# Sensor.net
KiCad netlist of a schematic drawn in Altium Designer
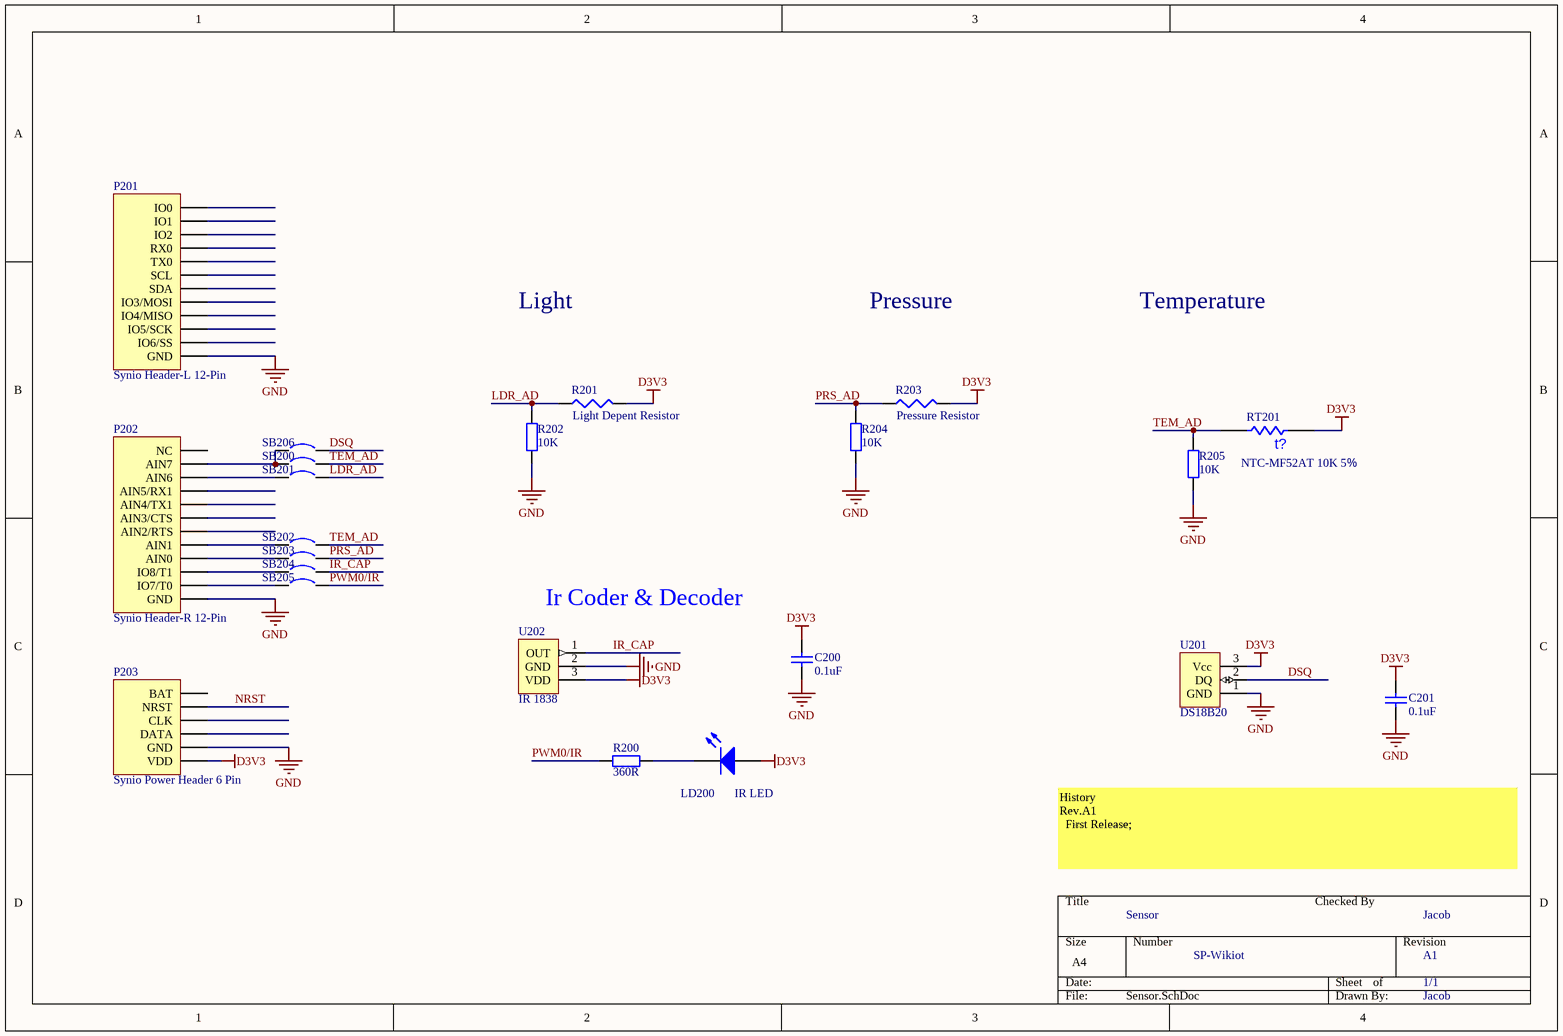
[diagram p0: Sensor.SchDoc]

(export (version "E")
  (design (tool "Eeschema 10.0.6"))
  (components
    (comp (ref "C200")
      (value "0.1uF")
      (footprint "0603M")
      (description "Capacitor")
      (fields (field (name "PUBLISHER") "Altium Limited"))
      (libsource (lib "Miscellaneous Devices") (part "Cap"))
    )
    (comp (ref "C201")
      (value "0.1uF")
      (footprint "0603M")
      (description "Capacitor")
      (fields (field (name "PUBLISHER") "Altium Limited"))
      (libsource (lib "Miscellaneous Devices") (part "Cap"))
    )
    (comp (ref "LD200")
      (value "IR LED")
      (footprint "HDR1X2/2.54mm")
      (description "Typical RED, GREEN, YELLOW, AMBER GaAs LED")
      (fields (field (name "PUBLISHER") "Altium Limited"))
      (libsource (lib "CT107D_SUDA") (part "LED"))
    )
    (comp (ref "P201")
      (value "Synio Header-L 12-Pin")
      (footprint "HDR1X12")
      (description "Synio Header-L, 12-Pin")
      (fields (field (name "PUBLISHER") "Altium Limited"))
      (libsource (lib "Connector") (part "Synio Header-L 12-Pin"))
    )
    (comp (ref "P202")
      (value "Synio Header-R 12-Pin")
      (footprint "HDR1X12")
      (description "Synio Header-R, 12-Pin")
      (fields (field (name "PUBLISHER") "Altium Limited"))
      (libsource (lib "Connector") (part "Synio Header-R 12-Pin"))
    )
    (comp (ref "P203")
      (value "Synio Power Header 6 Pin")
      (footprint "HDR1X6/2.54MM")
      (libsource (lib "Connector") (part "Synio Power Header 6 Pin"))
    )
    (comp (ref "R200")
      (value "360R")
      (footprint "0603M")
      (description "Resistor")
      (fields (field (name "PUBLISHER") "Altium Limited"))
      (libsource (lib "CT107D_SUDA") (part "Res"))
    )
    (comp (ref "R201")
      (value "Light Depent Resistor")
      (footprint "AXIAL-0.4")
      (description "Resistor")
      (fields (field (name "Comment") "Res3") (field (name "PUBLISHER") "Altium Limited"))
      (libsource (lib "Miscellaneous Devices") (part "Res3"))
    )
    (comp (ref "R202")
      (value "10K")
      (footprint "R0603")
      (description "Resistor")
      (fields (field (name "PUBLISHER") "Altium Limited"))
      (libsource (lib "Miscellaneous Devices") (part "Res2"))
    )
    (comp (ref "R203")
      (value "Pressure Resistor")
      (footprint "HDR1X2/2.54mm")
      (description "Resistor")
      (fields (field (name "Comment") "Res3") (field (name "PUBLISHER") "Altium Limited"))
      (libsource (lib "Miscellaneous Devices") (part "Res3"))
    )
    (comp (ref "R204")
      (value "10K")
      (footprint "R0603")
      (description "Resistor")
      (fields (field (name "PUBLISHER") "Altium Limited"))
      (libsource (lib "Miscellaneous Devices") (part "Res2"))
    )
    (comp (ref "R205")
      (value "10K")
      (footprint "R0603")
      (description "Resistor")
      (fields (field (name "PUBLISHER") "Altium Limited"))
      (libsource (lib "Miscellaneous Devices") (part "Res2"))
    )
    (comp (ref "RT201")
      (value "NTC-MF52AT 10K 5％")
      (footprint "HDR1X2/2.54mm")
      (description "Thermistor")
      (fields (field (name "PUBLISHER") "Altium Limited"))
      (libsource (lib "Miscellaneous Devices") (part "Res Thermal"))
    )
    (comp (ref "SB200")
      (value "Circuit Breaker")
      (footprint "JP2_SMD")
      (fields (field (name "PUBLISHER") "Altium Limited"))
      (libsource (lib "Misc") (part "Circuit Breaker"))
    )
    (comp (ref "SB201")
      (value "Circuit Breaker")
      (footprint "JP2_SMD")
      (fields (field (name "PUBLISHER") "Altium Limited"))
      (libsource (lib "Misc") (part "Circuit Breaker"))
    )
    (comp (ref "SB202")
      (value "Circuit Breaker")
      (footprint "JP2_SMD")
      (fields (field (name "PUBLISHER") "Altium Limited"))
      (libsource (lib "Misc") (part "Circuit Breaker"))
    )
    (comp (ref "SB203")
      (value "Circuit Breaker")
      (footprint "JP2_SMD")
      (fields (field (name "PUBLISHER") "Altium Limited"))
      (libsource (lib "Misc") (part "Circuit Breaker"))
    )
    (comp (ref "SB204")
      (value "Circuit Breaker")
      (footprint "JP2_SMD")
      (fields (field (name "PUBLISHER") "Altium Limited"))
      (libsource (lib "Misc") (part "Circuit Breaker"))
    )
    (comp (ref "SB205")
      (value "Circuit Breaker")
      (footprint "JP2_SMD")
      (fields (field (name "PUBLISHER") "Altium Limited"))
      (libsource (lib "Misc") (part "Circuit Breaker"))
    )
    (comp (ref "SB206")
      (value "Circuit Breaker")
      (footprint "JP2_SMD")
      (fields (field (name "PUBLISHER") "Altium Limited"))
      (libsource (lib "Misc") (part "Circuit Breaker"))
    )
    (comp (ref "U201")
      (value "DS18B20")
      (footprint "TO92")
      (description "Programmable Resolution  1-Wire Digital Thermometer")
      (fields (field (name "PUBLISHER") "Altium Limited"))
      (libsource (lib "CT107D_SUDA") (part "DS18B20"))
    )
    (comp (ref "U202")
      (value "IR 1838")
      (footprint "TSOP18")
      (description "Photo Modules for PCM Remote Control Systems")
      (fields (field (name "PUBLISHER") "Altium Limited"))
      (libsource (lib "CT107D_SUDA") (part "1838"))
    )
  )
  (nets
    (net (code "1") (name "/DSQ") (class "Default")
      (node (ref "SB206") (pin "2") (pinfunction "2_2") (pintype "passive"))
      (node (ref "U201") (pin "2") (pinfunction "DQ_2") (pintype "bidirectional"))
    )
    (net (code "2") (name "/IR_CAP") (class "Default")
      (node (ref "SB204") (pin "2") (pinfunction "2_2") (pintype "passive"))
      (node (ref "U202") (pin "1") (pinfunction "OUT_1") (pintype "output"))
    )
    (net (code "3") (name "/LDR_AD") (class "Default")
      (node (ref "R201") (pin "1") (pinfunction "1_1") (pintype "passive"))
      (node (ref "R202") (pin "2") (pinfunction "2_2") (pintype "passive"))
      (node (ref "SB201") (pin "2") (pinfunction "2_2") (pintype "passive"))
    )
    (net (code "4") (name "/NRST") (class "Default")
      (node (ref "P203") (pin "5") (pinfunction "NRST_5") (pintype "passive"))
    )
    (net (code "5") (name "/PRS_AD") (class "Default")
      (node (ref "R203") (pin "1") (pinfunction "1_1") (pintype "passive"))
      (node (ref "R204") (pin "2") (pinfunction "2_2") (pintype "passive"))
      (node (ref "SB203") (pin "2") (pinfunction "2_2") (pintype "passive"))
    )
    (net (code "6") (name "/PWM0{slash}IR") (class "Default")
      (node (ref "R200") (pin "2") (pinfunction "2_2") (pintype "passive"))
      (node (ref "SB205") (pin "2") (pinfunction "2_2") (pintype "passive"))
    )
    (net (code "7") (name "/TEM_AD") (class "Default")
      (node (ref "R205") (pin "2") (pinfunction "2_2") (pintype "passive"))
      (node (ref "RT201") (pin "2") (pinfunction "2_2") (pintype "passive"))
      (node (ref "SB200") (pin "2") (pinfunction "2_2") (pintype "passive"))
      (node (ref "SB202") (pin "2") (pinfunction "2_2") (pintype "passive"))
    )
    (net (code "8") (name "D3V3") (class "Default")
      (node (ref "C200") (pin "2") (pinfunction "2_2") (pintype "passive"))
      (node (ref "C201") (pin "2") (pinfunction "2_2") (pintype "passive"))
      (node (ref "LD200") (pin "1") (pinfunction "A_1") (pintype "passive"))
      (node (ref "P203") (pin "1") (pinfunction "VDD_1") (pintype "passive"))
      (node (ref "R201") (pin "2") (pinfunction "2_2") (pintype "passive"))
      (node (ref "R203") (pin "2") (pinfunction "2_2") (pintype "passive"))
      (node (ref "RT201") (pin "1") (pinfunction "1_1") (pintype "passive"))
      (node (ref "U201") (pin "3") (pinfunction "Vcc_3") (pintype "power_in"))
      (node (ref "U202") (pin "3") (pinfunction "VDD_3") (pintype "power_in"))
    )
    (net (code "9") (name "GND") (class "Default")
      (node (ref "C200") (pin "1") (pinfunction "1_1") (pintype "passive"))
      (node (ref "C201") (pin "1") (pinfunction "1_1") (pintype "passive"))
      (node (ref "P201") (pin "1") (pinfunction "GND_1") (pintype "passive"))
      (node (ref "P202") (pin "1") (pinfunction "GND_1") (pintype "passive"))
      (node (ref "P203") (pin "2") (pinfunction "GND_2") (pintype "passive"))
      (node (ref "R202") (pin "1") (pinfunction "1_1") (pintype "passive"))
      (node (ref "R204") (pin "1") (pinfunction "1_1") (pintype "passive"))
      (node (ref "R205") (pin "1") (pinfunction "1_1") (pintype "passive"))
      (node (ref "U201") (pin "1") (pinfunction "GND_1") (pintype "power_in"))
      (node (ref "U202") (pin "2") (pinfunction "GND_2") (pintype "power_in"))
    )
    (net (code "10") (name "Net-(LD200-K)") (class "Default")
      (node (ref "LD200") (pin "2") (pinfunction "K_2") (pintype "passive"))
      (node (ref "R200") (pin "1") (pinfunction "1_1") (pintype "passive"))
    )
    (net (code "11") (name "Net-(P202-AIN0)") (class "Default")
      (node (ref "P202") (pin "4") (pinfunction "AIN0_4") (pintype "passive"))
      (node (ref "SB203") (pin "1") (pinfunction "1_1") (pintype "passive"))
    )
    (net (code "12") (name "Net-(P202-AIN1)") (class "Default")
      (node (ref "P202") (pin "5") (pinfunction "AIN1_5") (pintype "passive"))
      (node (ref "SB202") (pin "1") (pinfunction "1_1") (pintype "passive"))
    )
    (net (code "13") (name "Net-(P202-AIN6)") (class "Default")
      (node (ref "P202") (pin "10") (pinfunction "AIN6_10") (pintype "passive"))
      (node (ref "SB201") (pin "1") (pinfunction "1_1") (pintype "passive"))
    )
    (net (code "14") (name "Net-(P202-AIN7)") (class "Default")
      (node (ref "P202") (pin "11") (pinfunction "AIN7_11") (pintype "passive"))
      (node (ref "SB200") (pin "1") (pinfunction "1_1") (pintype "passive"))
      (node (ref "SB206") (pin "1") (pinfunction "1_1") (pintype "passive"))
    )
    (net (code "15") (name "Net-(P202-IO7{slash}T0)") (class "Default")
      (node (ref "P202") (pin "2") (pinfunction "IO7/T0_2") (pintype "passive"))
      (node (ref "SB205") (pin "1") (pinfunction "1_1") (pintype "passive"))
    )
    (net (code "16") (name "Net-(P202-IO8{slash}T1)") (class "Default")
      (node (ref "P202") (pin "3") (pinfunction "IO8/T1_3") (pintype "passive"))
      (node (ref "SB204") (pin "1") (pinfunction "1_1") (pintype "passive"))
    )
    (net (code "17") (name "unconnected-(P201-IO0-Pad12)") (class "Default")
      (node (ref "P201") (pin "12") (pinfunction "IO0_12") (pintype "passive"))
    )
    (net (code "18") (name "unconnected-(P201-IO1-Pad11)") (class "Default")
      (node (ref "P201") (pin "11") (pinfunction "IO1_11") (pintype "passive"))
    )
    (net (code "19") (name "unconnected-(P201-IO2-Pad10)") (class "Default")
      (node (ref "P201") (pin "10") (pinfunction "IO2_10") (pintype "passive"))
    )
    (net (code "20") (name "unconnected-(P201-IO3{slash}MOSI-Pad5)") (class "Default")
      (node (ref "P201") (pin "5") (pinfunction "IO3/MOSI_5") (pintype "passive"))
    )
    (net (code "21") (name "unconnected-(P201-IO4{slash}MISO-Pad4)") (class "Default")
      (node (ref "P201") (pin "4") (pinfunction "IO4/MISO_4") (pintype "passive"))
    )
    (net (code "22") (name "unconnected-(P201-IO5{slash}SCK-Pad3)") (class "Default")
      (node (ref "P201") (pin "3") (pinfunction "IO5/SCK_3") (pintype "passive"))
    )
    (net (code "23") (name "unconnected-(P201-IO6{slash}SS-Pad2)") (class "Default")
      (node (ref "P201") (pin "2") (pinfunction "IO6/SS_2") (pintype "passive"))
    )
    (net (code "24") (name "unconnected-(P201-RX0-Pad9)") (class "Default")
      (node (ref "P201") (pin "9") (pinfunction "RX0_9") (pintype "passive"))
    )
    (net (code "25") (name "unconnected-(P201-SCL-Pad7)") (class "Default")
      (node (ref "P201") (pin "7") (pinfunction "SCL_7") (pintype "passive"))
    )
    (net (code "26") (name "unconnected-(P201-SDA-Pad6)") (class "Default")
      (node (ref "P201") (pin "6") (pinfunction "SDA_6") (pintype "passive"))
    )
    (net (code "27") (name "unconnected-(P201-TX0-Pad8)") (class "Default")
      (node (ref "P201") (pin "8") (pinfunction "TX0_8") (pintype "passive"))
    )
    (net (code "28") (name "unconnected-(P202-AIN2{slash}RTS-Pad6)") (class "Default")
      (node (ref "P202") (pin "6") (pinfunction "AIN2/RTS_6") (pintype "passive"))
    )
    (net (code "29") (name "unconnected-(P202-AIN3{slash}CTS-Pad7)") (class "Default")
      (node (ref "P202") (pin "7") (pinfunction "AIN3/CTS_7") (pintype "passive"))
    )
    (net (code "30") (name "unconnected-(P202-AIN4{slash}TX1-Pad8)") (class "Default")
      (node (ref "P202") (pin "8") (pinfunction "AIN4/TX1_8") (pintype "passive"))
    )
    (net (code "31") (name "unconnected-(P202-AIN5{slash}RX1-Pad9)") (class "Default")
      (node (ref "P202") (pin "9") (pinfunction "AIN5/RX1_9") (pintype "passive"))
    )
    (net (code "32") (name "unconnected-(P202-NC-Pad12)") (class "Default")
      (node (ref "P202") (pin "12") (pinfunction "NC_12") (pintype "passive"))
    )
    (net (code "33") (name "unconnected-(P203-BAT-Pad6)") (class "Default")
      (node (ref "P203") (pin "6") (pinfunction "BAT_6") (pintype "passive"))
    )
    (net (code "34") (name "unconnected-(P203-CLK-Pad4)") (class "Default")
      (node (ref "P203") (pin "4") (pinfunction "CLK_4") (pintype "passive"))
    )
    (net (code "35") (name "unconnected-(P203-DATA-Pad3)") (class "Default")
      (node (ref "P203") (pin "3") (pinfunction "DATA_3") (pintype "passive"))
    )
  )
)
